# espuno.net
KiCad netlist of a schematic drawn in EAGLE
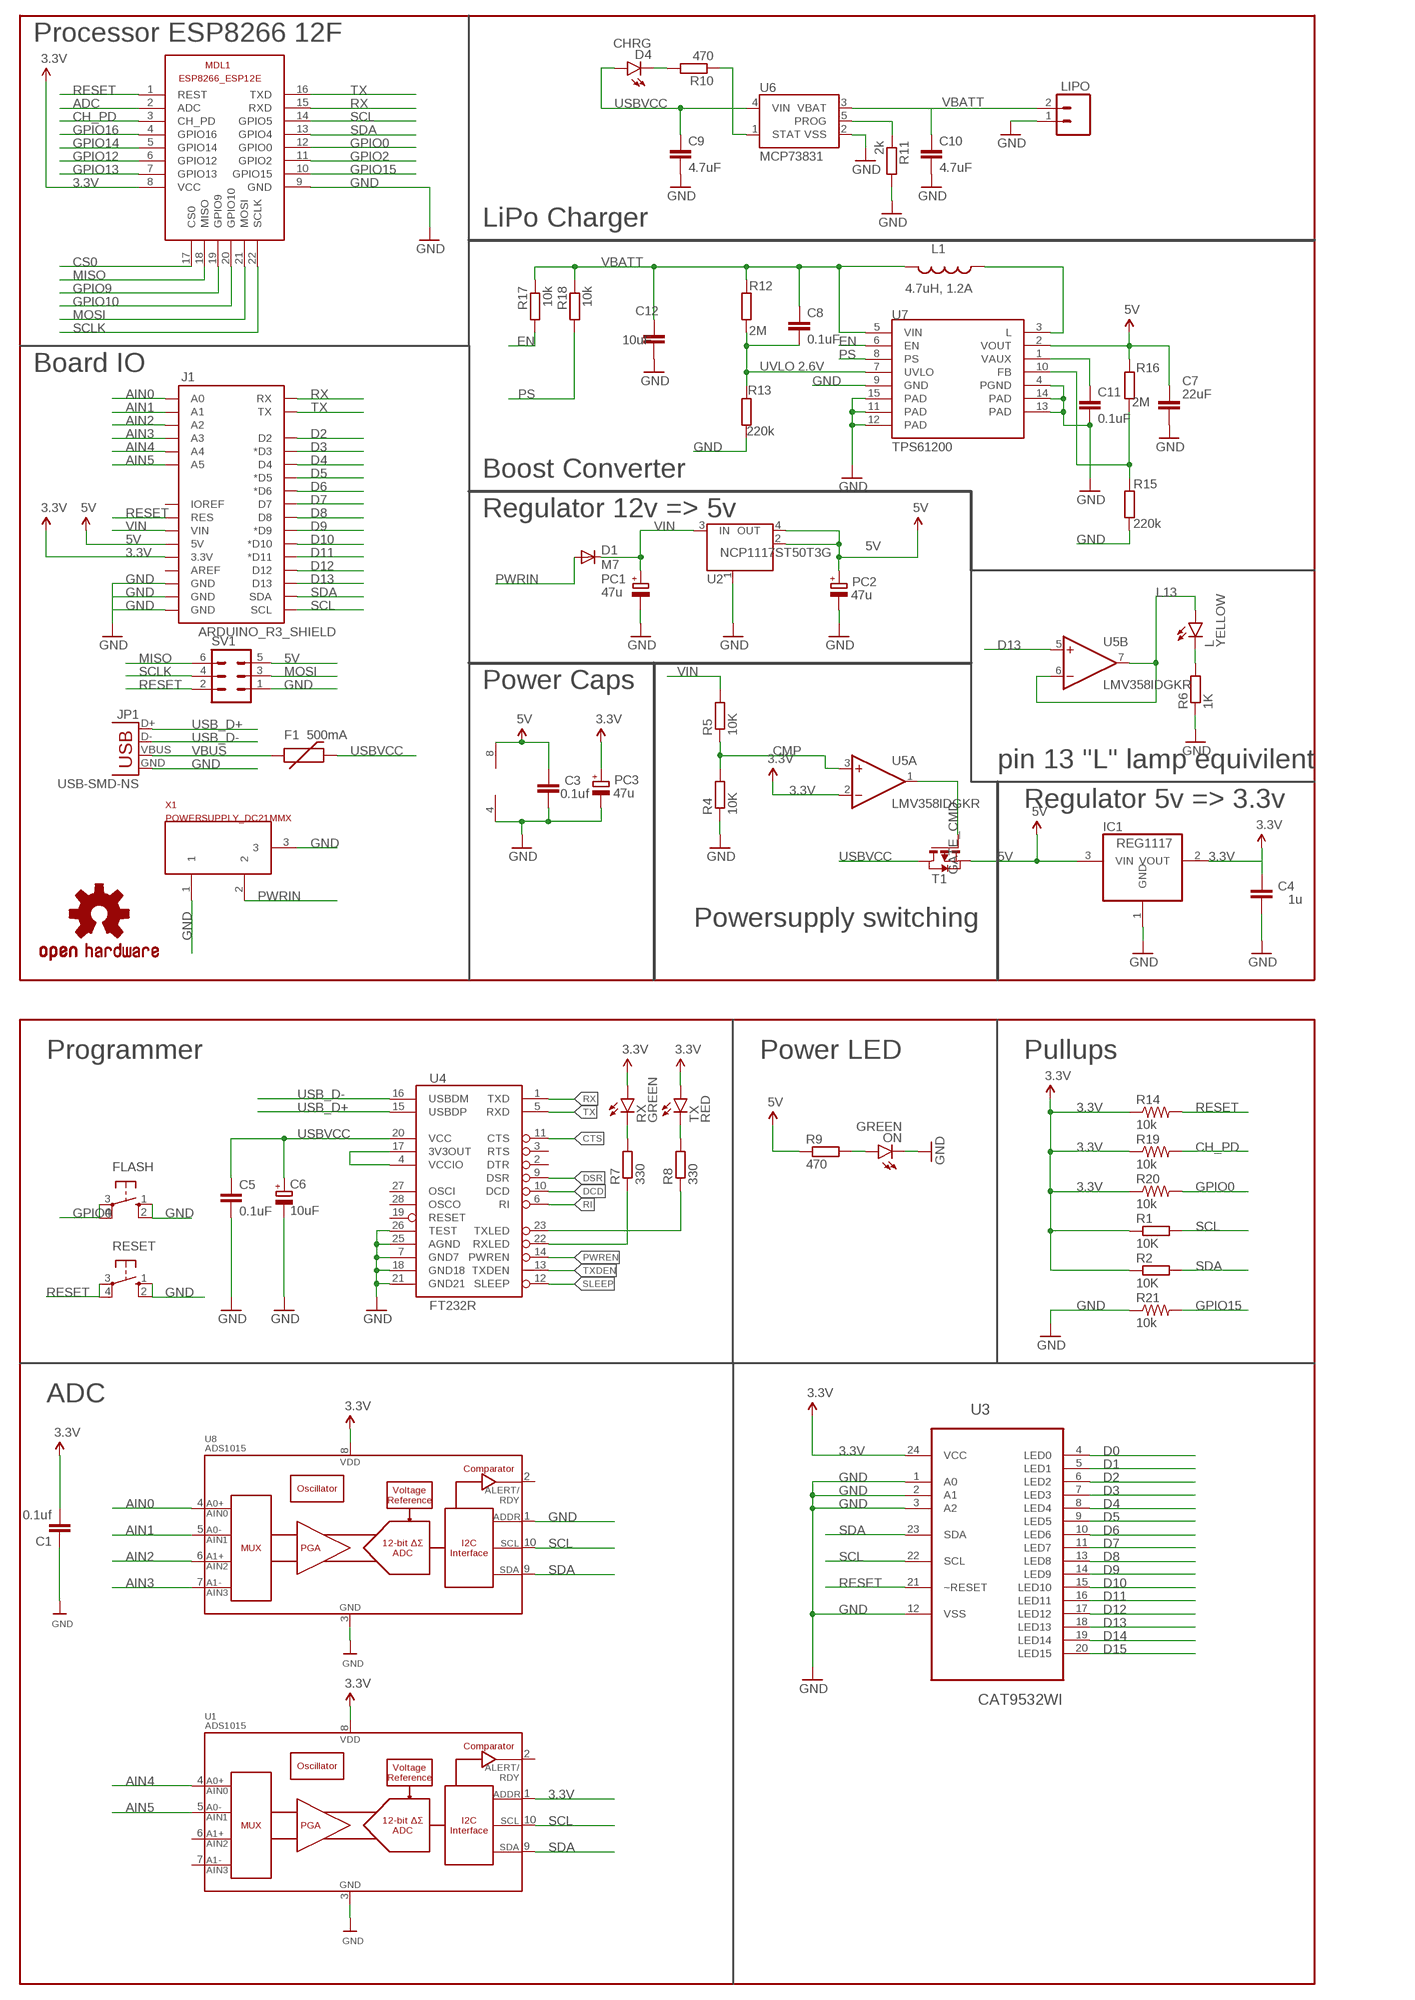
[diagram p0: schematic, sheet 1]

(export (version "E")
  (design (tool "Eeschema 10.0.6"))
  (components
    (comp (ref "C1")
      (value "0.1uf")
      (footprint "eagle-import:1206")
      (libsource (lib "eagle-import") (part "CAP1206"))
    )
    (comp (ref "C3")
      (value "0.1uf")
      (footprint "eagle-import:C1206K")
      (libsource (lib "eagle-import") (part "C-EUC1206K"))
    )
    (comp (ref "C4")
      (value "1u")
      (footprint "eagle-import:C1206K")
      (libsource (lib "eagle-import") (part "C-EUC1206K"))
    )
    (comp (ref "C5")
      (value "0.1uF")
      (footprint "eagle-import:C1206K")
      (libsource (lib "eagle-import") (part "C-EUC1206K"))
    )
    (comp (ref "C6")
      (value "10uF")
      (footprint "eagle-import:SMC_A")
      (libsource (lib "eagle-import") (part "CPOL-EUSMCA"))
    )
    (comp (ref "C7")
      (value "22uF")
      (footprint "eagle-import:C1206K")
      (libsource (lib "eagle-import") (part "C-EUC1206K"))
    )
    (comp (ref "C8")
      (value "0.1uF")
      (footprint "eagle-import:C1206K")
      (libsource (lib "eagle-import") (part "C-EUC1206K"))
    )
    (comp (ref "C9")
      (value "4.7uF")
      (footprint "eagle-import:C1206K")
      (libsource (lib "eagle-import") (part "C-EUC1206K"))
    )
    (comp (ref "C10")
      (value "4.7uF")
      (footprint "eagle-import:C1206K")
      (libsource (lib "eagle-import") (part "C-EUC1206K"))
    )
    (comp (ref "C11")
      (value "0.1uF")
      (footprint "eagle-import:C1206K")
      (libsource (lib "eagle-import") (part "C-EUC1206K"))
    )
    (comp (ref "C12")
      (value "10uF")
      (footprint "eagle-import:C1206K")
      (libsource (lib "eagle-import") (part "C-EUC1206K"))
    )
    (comp (ref "D1")
      (value "M7")
      (footprint "eagle-import:SMB")
      (libsource (lib "eagle-import") (part "DIODE-SMB"))
    )
    (comp (ref "D4")
      (value "CHRG")
      (footprint "eagle-import:LED-1206")
      (libsource (lib "eagle-import") (part "LED1206"))
    )
    (comp (ref "F1")
      (value "500mA")
      (footprint "eagle-import:PTC-1206")
      (libsource (lib "eagle-import") (part "PTCSMD"))
    )
    (comp (ref "FLASH")
      (value "10-XX")
      (footprint "eagle-import:B3F-10XX")
      (fields (field (name "MPN") "B3F-1000"))
      (libsource (lib "eagle-import") (part "10-XX"))
    )
    (comp (ref "FRAME1")
      (value "FRAME-LETTERNO_PACKAGE")
      (footprint "eagle-import:DUMMY")
      (fields (field (name "DESIGNER") "Nobody"))
      (libsource (lib "eagle-import") (part "FRAME-LETTERNO_PACKAGE"))
    )
    (comp (ref "FRAME2")
      (value "FRAME-LETTERNO_PACKAGE")
      (footprint "eagle-import:DUMMY")
      (fields (field (name "DESIGNER") "Nobody"))
      (libsource (lib "eagle-import") (part "FRAME-LETTERNO_PACKAGE"))
    )
    (comp (ref "IC1")
      (value "REG1117")
      (footprint "eagle-import:SOT223")
      (libsource (lib "eagle-import") (part "REG1117"))
    )
    (comp (ref "J1")
      (value "ARDUINO_R3_SHIELD")
      (footprint "eagle-import:UNO_R3_SHIELD")
      (libsource (lib "eagle-import") (part "ARDUINO_R3_SHIELD"))
    )
    (comp (ref "JP1")
      (value "USB-SMD-NS")
      (footprint "eagle-import:USB-MINIB-NOSTOP")
      (libsource (lib "eagle-import") (part "USB-SMD-NS"))
    )
    (comp (ref "L")
      (value "YELLOW")
      (footprint "eagle-import:LED-1206")
      (libsource (lib "eagle-import") (part "LED1206"))
    )
    (comp (ref "L1")
      (value "4.7uH, 1.2A")
      (footprint "eagle-import:CDRH2D09")
      (libsource (lib "eagle-import") (part "INDUCTOR."))
    )
    (comp (ref "LIPO")
      (value "M02JST-PTH-2")
      (footprint "eagle-import:JST-2-PTH")
      (libsource (lib "eagle-import") (part "M02JST-PTH-2"))
    )
    (comp (ref "LOGO1")
      (value "OSHW-LOGOS")
      (footprint "eagle-import:OSHW-LOGO-S")
      (libsource (lib "eagle-import") (part "OSHW-LOGOS"))
    )
    (comp (ref "MDL1")
      (value "ESP8266-12EESP8266-ESP12E")
      (footprint "eagle-import:ESP8266-ESP12E")
      (libsource (lib "eagle-import") (part "ESP8266-12EESP8266-ESP12E"))
    )
    (comp (ref "ON")
      (value "GREEN")
      (footprint "eagle-import:LED-1206")
      (libsource (lib "eagle-import") (part "LED1206"))
    )
    (comp (ref "PC1")
      (value "47u")
      (footprint "eagle-import:PANASONIC_D")
      (libsource (lib "eagle-import") (part "CPOL-EUD"))
    )
    (comp (ref "PC2")
      (value "47u")
      (footprint "eagle-import:PANASONIC_D")
      (libsource (lib "eagle-import") (part "CPOL-EUD"))
    )
    (comp (ref "PC3")
      (value "47u")
      (footprint "eagle-import:PANASONIC_D")
      (libsource (lib "eagle-import") (part "CPOL-EUD"))
    )
    (comp (ref "R1")
      (value "10K")
      (footprint "eagle-import:M1206")
      (libsource (lib "eagle-import") (part "R-EU_M1206"))
    )
    (comp (ref "R2")
      (value "10K")
      (footprint "eagle-import:M1206")
      (libsource (lib "eagle-import") (part "R-EU_M1206"))
    )
    (comp (ref "R4")
      (value "10K")
      (footprint "eagle-import:M1206")
      (libsource (lib "eagle-import") (part "R-EU_M1206"))
    )
    (comp (ref "R5")
      (value "10K")
      (footprint "eagle-import:M1206")
      (libsource (lib "eagle-import") (part "R-EU_M1206"))
    )
    (comp (ref "R6")
      (value "1K")
      (footprint "eagle-import:M1206")
      (libsource (lib "eagle-import") (part "R-EU_M1206"))
    )
    (comp (ref "R7")
      (value "330")
      (footprint "eagle-import:M1206")
      (libsource (lib "eagle-import") (part "R-EU_M1206"))
    )
    (comp (ref "R8")
      (value "330")
      (footprint "eagle-import:M1206")
      (libsource (lib "eagle-import") (part "R-EU_M1206"))
    )
    (comp (ref "R9")
      (value "470")
      (footprint "eagle-import:M1206")
      (libsource (lib "eagle-import") (part "R-EU_M1206"))
    )
    (comp (ref "R10")
      (value "470")
      (footprint "eagle-import:M1206")
      (libsource (lib "eagle-import") (part "R-EU_M1206"))
    )
    (comp (ref "R11")
      (value "2k")
      (footprint "eagle-import:M1206")
      (libsource (lib "eagle-import") (part "R-EU_M1206"))
    )
    (comp (ref "R12")
      (value "2M")
      (footprint "eagle-import:M1206")
      (libsource (lib "eagle-import") (part "R-EU_M1206"))
    )
    (comp (ref "R13")
      (value "220k")
      (footprint "eagle-import:M1206")
      (libsource (lib "eagle-import") (part "R-EU_M1206"))
    )
    (comp (ref "R14")
      (value "10k")
      (footprint "eagle-import:1206")
      (libsource (lib "eagle-import") (part "RESISTOR1206"))
    )
    (comp (ref "R15")
      (value "220k")
      (footprint "eagle-import:M1206")
      (libsource (lib "eagle-import") (part "R-EU_M1206"))
    )
    (comp (ref "R16")
      (value "2M")
      (footprint "eagle-import:M1206")
      (libsource (lib "eagle-import") (part "R-EU_M1206"))
    )
    (comp (ref "R17")
      (value "10k")
      (footprint "eagle-import:M1206")
      (libsource (lib "eagle-import") (part "R-EU_M1206"))
    )
    (comp (ref "R18")
      (value "10k")
      (footprint "eagle-import:M1206")
      (libsource (lib "eagle-import") (part "R-EU_M1206"))
    )
    (comp (ref "R19")
      (value "10k")
      (footprint "eagle-import:1206")
      (libsource (lib "eagle-import") (part "RESISTOR1206"))
    )
    (comp (ref "R20")
      (value "10k")
      (footprint "eagle-import:1206")
      (libsource (lib "eagle-import") (part "RESISTOR1206"))
    )
    (comp (ref "R21")
      (value "10k")
      (footprint "eagle-import:1206")
      (libsource (lib "eagle-import") (part "RESISTOR1206"))
    )
    (comp (ref "RESET")
      (value "10-XX")
      (footprint "eagle-import:B3F-10XX")
      (fields (field (name "MPN") "B3F-1000"))
      (libsource (lib "eagle-import") (part "10-XX"))
    )
    (comp (ref "RX")
      (value "GREEN")
      (footprint "eagle-import:LED-1206")
      (libsource (lib "eagle-import") (part "LED1206"))
    )
    (comp (ref "SV1")
      (value "MA03-2")
      (footprint "eagle-import:MA03-2")
      (libsource (lib "eagle-import") (part "MA03-2"))
    )
    (comp (ref "T1")
      (value "FDN340P")
      (footprint "eagle-import:SOT-23")
      (libsource (lib "eagle-import") (part "PMOSSOT23"))
    )
    (comp (ref "TX")
      (value "RED")
      (footprint "eagle-import:LED-1206")
      (libsource (lib "eagle-import") (part "LED1206"))
    )
    (comp (ref "U1")
      (value "ADS1015")
      (footprint "eagle-import:MSOP10")
      (libsource (lib "eagle-import") (part "ADS1015"))
    )
    (comp (ref "U2")
      (value "NCP1117ST50T3G")
      (footprint "eagle-import:SOT223")
      (libsource (lib "eagle-import") (part "MC33269ST-3.3T3"))
    )
    (comp (ref "U3")
      (value "CAT9532WI")
      (footprint "eagle-import:SOIC127P1031X265-24N")
      (fields (field (name "MPN") "CAT9532WI."))
      (libsource (lib "eagle-import") (part "CAT9532WI"))
    )
    (comp (ref "U4")
      (value "FT232R")
      (footprint "eagle-import:SSOP28DB")
      (libsource (lib "eagle-import") (part "FT232RLSSOP"))
    )
    (comp (ref "U5")
      (value "LMV358IDGKR")
      (footprint "eagle-import:MSOP08")
      (libsource (lib "eagle-import") (part "LMV358?MMX"))
    )
    (comp (ref "U6")
      (value "MCP73831")
      (footprint "eagle-import:SOT23-5")
      (libsource (lib "eagle-import") (part "MCP73831"))
    )
    (comp (ref "U7")
      (value "TPS61200")
      (footprint "eagle-import:QFN-10_PAD")
      (libsource (lib "eagle-import") (part "TPS61200"))
    )
    (comp (ref "U8")
      (value "ADS1015")
      (footprint "eagle-import:MSOP10")
      (libsource (lib "eagle-import") (part "ADS1015"))
    )
    (comp (ref "X1")
      (value "POWERSUPPLY_DC21MMX")
      (footprint "eagle-import:POWERSUPPLY_DC-21MM")
      (libsource (lib "eagle-import") (part "POWERSUPPLY_DC21MMX"))
    )
  )
  (nets
    (net (code "1") (name "/ADC") (class "Default")
      (node (ref "MDL1") (pin "2") (pinfunction "ADC_2") (pintype "bidirectional"))
    )
    (net (code "2") (name "/AIN0") (class "Default")
      (node (ref "J1") (pin "A0") (pinfunction "A0_A0") (pintype "bidirectional"))
      (node (ref "U8") (pin "4") (pinfunction "AIN0_4") (pintype "bidirectional"))
    )
    (net (code "3") (name "/AIN1") (class "Default")
      (node (ref "J1") (pin "A1") (pinfunction "A1_A1") (pintype "bidirectional"))
      (node (ref "U8") (pin "5") (pinfunction "AIN1_5") (pintype "bidirectional"))
    )
    (net (code "4") (name "/AIN2") (class "Default")
      (node (ref "J1") (pin "A2") (pinfunction "A2_A2") (pintype "bidirectional"))
      (node (ref "U8") (pin "6") (pinfunction "AIN2_6") (pintype "bidirectional"))
    )
    (net (code "5") (name "/AIN3") (class "Default")
      (node (ref "J1") (pin "A3") (pinfunction "A3_A3") (pintype "bidirectional"))
      (node (ref "U8") (pin "7") (pinfunction "AIN3_7") (pintype "bidirectional"))
    )
    (net (code "6") (name "/AIN4") (class "Default")
      (node (ref "J1") (pin "A4") (pinfunction "A4_A4") (pintype "bidirectional"))
      (node (ref "U1") (pin "4") (pinfunction "AIN0_4") (pintype "bidirectional"))
    )
    (net (code "7") (name "/AIN5") (class "Default")
      (node (ref "J1") (pin "A5") (pinfunction "A5_A5") (pintype "bidirectional"))
      (node (ref "U1") (pin "5") (pinfunction "AIN1_5") (pintype "bidirectional"))
    )
    (net (code "8") (name "/CH_PD") (class "Default")
      (node (ref "MDL1") (pin "3") (pinfunction "CH_PD_3") (pintype "bidirectional"))
      (node (ref "R19") (pin "2") (pinfunction "2_2") (pintype "passive"))
    )
    (net (code "9") (name "/CMP") (class "Default")
      (node (ref "R4") (pin "2") (pinfunction "2_2") (pintype "passive"))
      (node (ref "R5") (pin "1") (pinfunction "1_1") (pintype "passive"))
      (node (ref "U5") (pin "3") (pinfunction "+IN_3") (pintype "input"))
    )
    (net (code "10") (name "/CS0") (class "Default")
      (node (ref "MDL1") (pin "17") (pinfunction "CS0_17") (pintype "bidirectional"))
    )
    (net (code "11") (name "/D0") (class "Default")
      (node (ref "U3") (pin "4") (pinfunction "LED0_4") (pintype "output"))
    )
    (net (code "12") (name "/D1") (class "Default")
      (node (ref "U3") (pin "5") (pinfunction "LED1_5") (pintype "output"))
    )
    (net (code "13") (name "/D2") (class "Default")
      (node (ref "J1") (pin "D2") (pinfunction "D2_D2") (pintype "bidirectional"))
      (node (ref "U3") (pin "6") (pinfunction "LED2_6") (pintype "output"))
    )
    (net (code "14") (name "/D3") (class "Default")
      (node (ref "J1") (pin "D3") (pinfunction "*D3_D3") (pintype "bidirectional"))
      (node (ref "U3") (pin "7") (pinfunction "LED3_7") (pintype "output"))
    )
    (net (code "15") (name "/D4") (class "Default")
      (node (ref "J1") (pin "D4") (pinfunction "D4_D4") (pintype "bidirectional"))
      (node (ref "U3") (pin "8") (pinfunction "LED4_8") (pintype "output"))
    )
    (net (code "16") (name "/D5") (class "Default")
      (node (ref "J1") (pin "D5") (pinfunction "*D5_D5") (pintype "bidirectional"))
      (node (ref "U3") (pin "9") (pinfunction "LED5_9") (pintype "output"))
    )
    (net (code "17") (name "/D6") (class "Default")
      (node (ref "J1") (pin "D6") (pinfunction "*D6_D6") (pintype "bidirectional"))
      (node (ref "U3") (pin "10") (pinfunction "LED6_10") (pintype "output"))
    )
    (net (code "18") (name "/D7") (class "Default")
      (node (ref "J1") (pin "D7") (pinfunction "D7_D7") (pintype "bidirectional"))
      (node (ref "U3") (pin "11") (pinfunction "LED7_11") (pintype "output"))
    )
    (net (code "19") (name "/D8") (class "Default")
      (node (ref "J1") (pin "D8") (pinfunction "D8_D8") (pintype "bidirectional"))
      (node (ref "U3") (pin "13") (pinfunction "LED8_13") (pintype "output"))
    )
    (net (code "20") (name "/D9") (class "Default")
      (node (ref "J1") (pin "D9") (pinfunction "*D9_D9") (pintype "bidirectional"))
      (node (ref "U3") (pin "14") (pinfunction "LED9_14") (pintype "output"))
    )
    (net (code "21") (name "/D10") (class "Default")
      (node (ref "J1") (pin "D10") (pinfunction "*D10_D10") (pintype "bidirectional"))
      (node (ref "U3") (pin "15") (pinfunction "LED10_15") (pintype "output"))
    )
    (net (code "22") (name "/D11") (class "Default")
      (node (ref "J1") (pin "D11") (pinfunction "*D11_D11") (pintype "bidirectional"))
      (node (ref "U3") (pin "16") (pinfunction "LED11_16") (pintype "output"))
    )
    (net (code "23") (name "/D12") (class "Default")
      (node (ref "J1") (pin "D12") (pinfunction "D12_D12") (pintype "bidirectional"))
      (node (ref "U3") (pin "17") (pinfunction "LED12_17") (pintype "output"))
    )
    (net (code "24") (name "/D13") (class "Default")
      (node (ref "J1") (pin "D13") (pinfunction "D13_D13") (pintype "bidirectional"))
      (node (ref "U3") (pin "18") (pinfunction "LED13_18") (pintype "output"))
      (node (ref "U5") (pin "5") (pinfunction "+IN_5") (pintype "input"))
    )
    (net (code "25") (name "/D14") (class "Default")
      (node (ref "U3") (pin "19") (pinfunction "LED14_19") (pintype "output"))
    )
    (net (code "26") (name "/D15") (class "Default")
      (node (ref "U3") (pin "20") (pinfunction "LED15_20") (pintype "output"))
    )
    (net (code "27") (name "/EN") (class "Default")
      (node (ref "R17") (pin "2") (pinfunction "2_2") (pintype "passive"))
      (node (ref "U7") (pin "6") (pinfunction "EN_6") (pintype "input"))
    )
    (net (code "28") (name "/GATE_CMD") (class "Default")
      (node (ref "T1") (pin "3") (pinfunction "G_3") (pintype "passive"))
      (node (ref "U5") (pin "1") (pinfunction "OUT_1") (pintype "output"))
    )
    (net (code "29") (name "/GPIO0") (class "Default")
      (node (ref "FLASH") (pin "3") (pinfunction "P_3") (pintype "passive"))
      (node (ref "FLASH") (pin "4") (pinfunction "P1_4") (pintype "passive"))
      (node (ref "MDL1") (pin "12") (pinfunction "GPIO0_12") (pintype "bidirectional"))
      (node (ref "R20") (pin "2") (pinfunction "2_2") (pintype "passive"))
    )
    (net (code "30") (name "/GPIO2") (class "Default")
      (node (ref "MDL1") (pin "11") (pinfunction "GPIO2_11") (pintype "bidirectional"))
    )
    (net (code "31") (name "/GPIO9") (class "Default")
      (node (ref "MDL1") (pin "19") (pinfunction "GPIO9_19") (pintype "bidirectional"))
    )
    (net (code "32") (name "/GPIO10") (class "Default")
      (node (ref "MDL1") (pin "20") (pinfunction "GPIO10_20") (pintype "bidirectional"))
    )
    (net (code "33") (name "/GPIO12") (class "Default")
      (node (ref "MDL1") (pin "6") (pinfunction "GPIO12_6") (pintype "bidirectional"))
    )
    (net (code "34") (name "/GPIO13") (class "Default")
      (node (ref "MDL1") (pin "7") (pinfunction "GPIO13_7") (pintype "bidirectional"))
    )
    (net (code "35") (name "/GPIO14") (class "Default")
      (node (ref "MDL1") (pin "5") (pinfunction "GPIO14_5") (pintype "bidirectional"))
    )
    (net (code "36") (name "/GPIO15") (class "Default")
      (node (ref "MDL1") (pin "10") (pinfunction "GPIO15_10") (pintype "bidirectional"))
      (node (ref "R21") (pin "2") (pinfunction "2_2") (pintype "passive"))
    )
    (net (code "37") (name "/GPIO16") (class "Default")
      (node (ref "MDL1") (pin "4") (pinfunction "GPIO16_4") (pintype "bidirectional"))
    )
    (net (code "38") (name "/L13") (class "Default")
      (node (ref "L") (pin "A") (pinfunction "A_A") (pintype "passive"))
      (node (ref "U5") (pin "6") (pinfunction "-IN_6") (pintype "input"))
      (node (ref "U5") (pin "7") (pinfunction "OUT_7") (pintype "output"))
    )
    (net (code "39") (name "/MISO") (class "Default")
      (node (ref "MDL1") (pin "18") (pinfunction "MISO_18") (pintype "bidirectional"))
      (node (ref "SV1") (pin "6") (pinfunction "6_6") (pintype "passive"))
    )
    (net (code "40") (name "/MOSI") (class "Default")
      (node (ref "MDL1") (pin "21") (pinfunction "MOSI_21") (pintype "bidirectional"))
      (node (ref "SV1") (pin "3") (pinfunction "3_3") (pintype "passive"))
    )
    (net (code "41") (name "/PS") (class "Default")
      (node (ref "R18") (pin "2") (pinfunction "2_2") (pintype "passive"))
      (node (ref "U7") (pin "8") (pinfunction "PS_8") (pintype "input"))
    )
    (net (code "42") (name "/PWRIN") (class "Default")
      (node (ref "D1") (pin "A") (pinfunction "A_A") (pintype "passive"))
      (node (ref "X1") (pin "2") (pinfunction "2_2") (pintype "power_in"))
    )
    (net (code "43") (name "/RESET") (class "Default")
      (node (ref "J1") (pin "RES") (pinfunction "RES_RES") (pintype "bidirectional"))
      (node (ref "MDL1") (pin "1") (pinfunction "REST_1") (pintype "bidirectional"))
      (node (ref "R14") (pin "2") (pinfunction "2_2") (pintype "passive"))
      (node (ref "RESET") (pin "3") (pinfunction "P_3") (pintype "passive"))
      (node (ref "RESET") (pin "4") (pinfunction "P1_4") (pintype "passive"))
      (node (ref "SV1") (pin "2") (pinfunction "2_2") (pintype "passive"))
      (node (ref "U3") (pin "21") (pinfunction "~{RESET}_21") (pintype "input"))
    )
    (net (code "44") (name "/SCL") (class "Default")
      (node (ref "J1") (pin "SCL") (pinfunction "SCL_SCL") (pintype "bidirectional"))
      (node (ref "MDL1") (pin "14") (pinfunction "GPIO5_14") (pintype "bidirectional"))
      (node (ref "R1") (pin "2") (pinfunction "2_2") (pintype "passive"))
      (node (ref "U1") (pin "10") (pinfunction "SCL_10") (pintype "bidirectional"))
      (node (ref "U3") (pin "22") (pinfunction "SCL_22") (pintype "input"))
      (node (ref "U8") (pin "10") (pinfunction "SCL_10") (pintype "bidirectional"))
    )
    (net (code "45") (name "/SCLK") (class "Default")
      (node (ref "MDL1") (pin "22") (pinfunction "SCLK_22") (pintype "bidirectional"))
      (node (ref "SV1") (pin "4") (pinfunction "4_4") (pintype "passive"))
    )
    (net (code "46") (name "/SDA") (class "Default")
      (node (ref "J1") (pin "SDA") (pinfunction "SDA_SDA") (pintype "bidirectional"))
      (node (ref "MDL1") (pin "13") (pinfunction "GPIO4_13") (pintype "bidirectional"))
      (node (ref "R2") (pin "2") (pinfunction "2_2") (pintype "passive"))
      (node (ref "U1") (pin "9") (pinfunction "SDA_9") (pintype "bidirectional"))
      (node (ref "U3") (pin "23") (pinfunction "SDA_23") (pintype "input"))
      (node (ref "U8") (pin "9") (pinfunction "SDA_9") (pintype "bidirectional"))
    )
    (net (code "47") (name "/USBVCC") (class "Default")
      (node (ref "C5") (pin "1") (pinfunction "1_1") (pintype "passive"))
      (node (ref "C6") (pin "+") (pinfunction "+_+") (pintype "passive"))
      (node (ref "C9") (pin "1") (pinfunction "1_1") (pintype "passive"))
      (node (ref "D4") (pin "A") (pinfunction "A_A") (pintype "passive"))
      (node (ref "F1") (pin "2") (pinfunction "2_2") (pintype "bidirectional"))
      (node (ref "T1") (pin "1") (pinfunction "D_1") (pintype "passive"))
      (node (ref "U4") (pin "20") (pinfunction "VCC_20") (pintype "power_in"))
      (node (ref "U6") (pin "4") (pinfunction "VIN_4") (pintype "power_in"))
    )
    (net (code "48") (name "/USB_D+") (class "Default")
      (node (ref "JP1") (pin "D+") (pinfunction "D+_D+") (pintype "bidirectional"))
      (node (ref "U4") (pin "15") (pinfunction "USBDP_15") (pintype "bidirectional"))
    )
    (net (code "49") (name "/USB_D-") (class "Default")
      (node (ref "JP1") (pin "D-") (pinfunction "D-_D-") (pintype "bidirectional"))
      (node (ref "U4") (pin "16") (pinfunction "USBDM_16") (pintype "bidirectional"))
    )
    (net (code "50") (name "/VBATT") (class "Default")
      (node (ref "C10") (pin "1") (pinfunction "1_1") (pintype "passive"))
      (node (ref "C12") (pin "1") (pinfunction "1_1") (pintype "passive"))
      (node (ref "C8") (pin "1") (pinfunction "1_1") (pintype "passive"))
      (node (ref "L1") (pin "P$2") (pinfunction "2_P$2") (pintype "passive"))
      (node (ref "LIPO") (pin "2") (pinfunction "2_2") (pintype "passive"))
      (node (ref "R12") (pin "2") (pinfunction "2_2") (pintype "passive"))
      (node (ref "R17") (pin "1") (pinfunction "1_1") (pintype "passive"))
      (node (ref "R18") (pin "1") (pinfunction "1_1") (pintype "passive"))
      (node (ref "U6") (pin "3") (pinfunction "VBAT_3") (pintype "power_in"))
      (node (ref "U7") (pin "5") (pinfunction "VIN_5") (pintype "power_in"))
    )
    (net (code "51") (name "/VBUS") (class "Default")
      (node (ref "F1") (pin "1") (pinfunction "1_1") (pintype "bidirectional"))
      (node (ref "JP1") (pin "VBUS") (pinfunction "VBUS_VBUS") (pintype "bidirectional"))
    )
    (net (code "52") (name "/VIN") (class "Default")
      (node (ref "D1") (pin "C") (pinfunction "C_C") (pintype "passive"))
      (node (ref "J1") (pin "VIN") (pinfunction "VIN_VIN") (pintype "bidirectional"))
      (node (ref "PC1") (pin "+") (pinfunction "+_+") (pintype "passive"))
      (node (ref "R5") (pin "2") (pinfunction "2_2") (pintype "passive"))
      (node (ref "U2") (pin "3") (pinfunction "IN_3") (pintype "input"))
    )
    (net (code "53") (name "3.3V") (class "Default")
      (node (ref "C1") (pin "2") (pinfunction "2_2") (pintype "passive"))
      (node (ref "C4") (pin "2") (pinfunction "2_2") (pintype "passive"))
      (node (ref "IC1") (pin "2") (pinfunction "VOUT_2") (pintype "output"))
      (node (ref "J1") (pin "3.3V") (pinfunction "3.3V_3.3V") (pintype "bidirectional"))
      (node (ref "MDL1") (pin "8") (pinfunction "VCC_8") (pintype "bidirectional"))
      (node (ref "PC3") (pin "+") (pinfunction "+_+") (pintype "passive"))
      (node (ref "R1") (pin "1") (pinfunction "1_1") (pintype "passive"))
      (node (ref "R14") (pin "1") (pinfunction "1_1") (pintype "passive"))
      (node (ref "R19") (pin "1") (pinfunction "1_1") (pintype "passive"))
      (node (ref "R2") (pin "1") (pinfunction "1_1") (pintype "passive"))
      (node (ref "R20") (pin "1") (pinfunction "1_1") (pintype "passive"))
      (node (ref "RX") (pin "A") (pinfunction "A_A") (pintype "passive"))
      (node (ref "TX") (pin "A") (pinfunction "A_A") (pintype "passive"))
      (node (ref "U1") (pin "1") (pinfunction "ADDR_1") (pintype "bidirectional"))
      (node (ref "U1") (pin "8") (pinfunction "VDD_8") (pintype "bidirectional"))
      (node (ref "U3") (pin "24") (pinfunction "VCC_24") (pintype "power_in"))
      (node (ref "U5") (pin "2") (pinfunction "-IN_2") (pintype "input"))
      (node (ref "U8") (pin "8") (pinfunction "VDD_8") (pintype "bidirectional"))
    )
    (net (code "54") (name "5V") (class "Default")
      (node (ref "C3") (pin "2") (pinfunction "2_2") (pintype "passive"))
      (node (ref "C7") (pin "1") (pinfunction "1_1") (pintype "passive"))
      (node (ref "IC1") (pin "3") (pinfunction "VIN_3") (pintype "input"))
      (node (ref "J1") (pin "5V") (pinfunction "5V_5V") (pintype "bidirectional"))
      (node (ref "PC2") (pin "+") (pinfunction "+_+") (pintype "passive"))
      (node (ref "R16") (pin "2") (pinfunction "2_2") (pintype "passive"))
      (node (ref "R9") (pin "1") (pinfunction "1_1") (pintype "passive"))
      (node (ref "SV1") (pin "5") (pinfunction "5_5") (pintype "passive"))
      (node (ref "T1") (pin "2") (pinfunction "S_2") (pintype "passive"))
      (node (ref "U2") (pin "2") (pinfunction "OUT_2") (pintype "passive"))
      (node (ref "U2") (pin "4") (pinfunction "OUT_4") (pintype "passive"))
      (node (ref "U5") (pin "8") (pinfunction "V+_8") (pintype "power_in"))
      (node (ref "U7") (pin "2") (pinfunction "VOUT_2") (pintype "passive"))
    )
    (net (code "55") (name "CTS") (class "Default")
      (node (ref "U4") (pin "11") (pinfunction "CTS_11") (pintype "input"))
    )
    (net (code "56") (name "DCD") (class "Default")
      (node (ref "U4") (pin "10") (pinfunction "DCD_10") (pintype "input"))
    )
    (net (code "57") (name "DSR") (class "Default")
      (node (ref "U4") (pin "9") (pinfunction "DSR_9") (pintype "input"))
    )
    (net (code "58") (name "GND") (class "Default")
      (node (ref "C1") (pin "1") (pinfunction "1_1") (pintype "passive"))
      (node (ref "C10") (pin "2") (pinfunction "2_2") (pintype "passive"))
      (node (ref "C11") (pin "2") (pinfunction "2_2") (pintype "passive"))
      (node (ref "C12") (pin "2") (pinfunction "2_2") (pintype "passive"))
      (node (ref "C3") (pin "1") (pinfunction "1_1") (pintype "passive"))
      (node (ref "C4") (pin "1") (pinfunction "1_1") (pintype "passive"))
      (node (ref "C5") (pin "2") (pinfunction "2_2") (pintype "passive"))
      (node (ref "C6") (pin "-") (pinfunction "-_-") (pintype "passive"))
      (node (ref "C7") (pin "2") (pinfunction "2_2") (pintype "passive"))
      (node (ref "C9") (pin "2") (pinfunction "2_2") (pintype "passive"))
      (node (ref "FLASH") (pin "1") (pinfunction "S_1") (pintype "passive"))
      (node (ref "FLASH") (pin "2") (pinfunction "S1_2") (pintype "passive"))
      (node (ref "IC1") (pin "1") (pinfunction "GND_1") (pintype "power_in"))
      (node (ref "J1") (pin "GND@0") (pinfunction "GND_GND@0") (pintype "bidirectional"))
      (node (ref "J1") (pin "GND@1") (pinfunction "GND_GND@1") (pintype "bidirectional"))
      (node (ref "J1") (pin "GND@2") (pinfunction "GND_GND@2") (pintype "bidirectional"))
      (node (ref "JP1") (pin "GND") (pinfunction "GND_GND") (pintype "bidirectional"))
      (node (ref "LIPO") (pin "1") (pinfunction "1_1") (pintype "passive"))
      (node (ref "MDL1") (pin "9") (pinfunction "GND_9") (pintype "bidirectional"))
      (node (ref "ON") (pin "C") (pinfunction "C_C") (pintype "passive"))
      (node (ref "PC1") (pin "-") (pinfunction "-_-") (pintype "passive"))
      (node (ref "PC2") (pin "-") (pinfunction "-_-") (pintype "passive"))
      (node (ref "PC3") (pin "-") (pinfunction "-_-") (pintype "passive"))
      (node (ref "R11") (pin "2") (pinfunction "2_2") (pintype "passive"))
      (node (ref "R13") (pin "1") (pinfunction "1_1") (pintype "passive"))
      (node (ref "R15") (pin "1") (pinfunction "1_1") (pintype "passive"))
      (node (ref "R21") (pin "1") (pinfunction "1_1") (pintype "passive"))
      (node (ref "R4") (pin "1") (pinfunction "1_1") (pintype "passive"))
      (node (ref "R6") (pin "1") (pinfunction "1_1") (pintype "passive"))
      (node (ref "RESET") (pin "1") (pinfunction "S_1") (pintype "passive"))
      (node (ref "RESET") (pin "2") (pinfunction "S1_2") (pintype "passive"))
      (node (ref "SV1") (pin "1") (pinfunction "1_1") (pintype "passive"))
      (node (ref "U1") (pin "3") (pinfunction "VSS_3") (pintype "bidirectional"))
      (node (ref "U2") (pin "1") (pinfunction "GND/ADJ_1") (pintype "input"))
      (node (ref "U3") (pin "1") (pinfunction "A0_1") (pintype "input"))
      (node (ref "U3") (pin "12") (pinfunction "VSS_12") (pintype "input"))
      (node (ref "U3") (pin "2") (pinfunction "A1_2") (pintype "input"))
      (node (ref "U3") (pin "3") (pinfunction "A2_3") (pintype "input"))
      (node (ref "U4") (pin "18") (pinfunction "GND18_18") (pintype "power_in"))
      (node (ref "U4") (pin "21") (pinfunction "GND21_21") (pintype "power_in"))
      (node (ref "U4") (pin "25") (pinfunction "AGND_25") (pintype "power_in"))
      (node (ref "U4") (pin "26") (pinfunction "TEST_26") (pintype "input"))
      (node (ref "U4") (pin "7") (pinfunction "GND7_7") (pintype "power_in"))
      (node (ref "U5") (pin "4") (pinfunction "V-_4") (pintype "power_in"))
      (node (ref "U6") (pin "2") (pinfunction "VSS_2") (pintype "power_in"))
      (node (ref "U7") (pin "11") (pinfunction "PAD_11") (pintype "power_in"))
      (node (ref "U7") (pin "12") (pinfunction "PAD_12") (pintype "power_in"))
      (node (ref "U7") (pin "13") (pinfunction "PAD_13") (pintype "power_in"))
      (node (ref "U7") (pin "14") (pinfunction "PAD_14") (pintype "power_in"))
      (node (ref "U7") (pin "15") (pinfunction "PAD_15") (pintype "power_in"))
      (node (ref "U7") (pin "4") (pinfunction "PGND_4") (pintype "power_in"))
      (node (ref "U7") (pin "9") (pinfunction "GND_9") (pintype "power_in"))
      (node (ref "U8") (pin "1") (pinfunction "ADDR_1") (pintype "bidirectional"))
      (node (ref "U8") (pin "3") (pinfunction "VSS_3") (pintype "bidirectional"))
      (node (ref "X1") (pin "1") (pinfunction "1_1") (pintype "power_in"))
      (node (ref "X1") (pin "3") (pinfunction "3_3") (pintype "power_in"))
    )
    (net (code "59") (name "Net-(D4-PadC)") (class "Default")
      (node (ref "D4") (pin "C") (pinfunction "C_C") (pintype "passive"))
      (node (ref "R10") (pin "2") (pinfunction "2_2") (pintype "passive"))
    )
    (net (code "60") (name "Net-(L-PadC)") (class "Default")
      (node (ref "L") (pin "C") (pinfunction "C_C") (pintype "passive"))
      (node (ref "R6") (pin "2") (pinfunction "2_2") (pintype "passive"))
    )
    (net (code "61") (name "Net-(L1-1)") (class "Default")
      (node (ref "L1") (pin "P$1") (pinfunction "1_P$1") (pintype "passive"))
      (node (ref "U7") (pin "3") (pinfunction "L_3") (pintype "passive"))
    )
    (net (code "62") (name "Net-(ON-PadA)") (class "Default")
      (node (ref "ON") (pin "A") (pinfunction "A_A") (pintype "passive"))
      (node (ref "R9") (pin "2") (pinfunction "2_2") (pintype "passive"))
    )
    (net (code "63") (name "Net-(R7-Pad2)") (class "Default")
      (node (ref "R7") (pin "2") (pinfunction "2_2") (pintype "passive"))
      (node (ref "RX") (pin "C") (pinfunction "C_C") (pintype "passive"))
    )
    (net (code "64") (name "Net-(R8-Pad2)") (class "Default")
      (node (ref "R8") (pin "2") (pinfunction "2_2") (pintype "passive"))
      (node (ref "TX") (pin "C") (pinfunction "C_C") (pintype "passive"))
    )
    (net (code "65") (name "Net-(U4-3V3OUT)") (class "Default")
      (node (ref "U4") (pin "17") (pinfunction "3V3OUT_17") (pintype "output"))
      (node (ref "U4") (pin "4") (pinfunction "VCCIO_4") (pintype "power_in"))
    )
    (net (code "66") (name "Net-(U4-RXLED)") (class "Default")
      (node (ref "R7") (pin "1") (pinfunction "1_1") (pintype "passive"))
      (node (ref "U4") (pin "22") (pinfunction "RXLED_22") (pintype "input"))
    )
    (net (code "67") (name "Net-(U4-TXLED)") (class "Default")
      (node (ref "R8") (pin "1") (pinfunction "1_1") (pintype "passive"))
      (node (ref "U4") (pin "23") (pinfunction "TXLED_23") (pintype "input"))
    )
    (net (code "68") (name "Net-(U6-PROG)") (class "Default")
      (node (ref "R11") (pin "1") (pinfunction "1_1") (pintype "passive"))
      (node (ref "U6") (pin "5") (pinfunction "PROG_5") (pintype "input"))
    )
    (net (code "69") (name "Net-(U6-STAT)") (class "Default")
      (node (ref "R10") (pin "1") (pinfunction "1_1") (pintype "passive"))
      (node (ref "U6") (pin "1") (pinfunction "STAT_1") (pintype "output"))
    )
    (net (code "70") (name "Net-(U7-FB)") (class "Default")
      (node (ref "R15") (pin "2") (pinfunction "2_2") (pintype "passive"))
      (node (ref "R16") (pin "1") (pinfunction "1_1") (pintype "passive"))
      (node (ref "U7") (pin "10") (pinfunction "FB_10") (pintype "passive"))
    )
    (net (code "71") (name "Net-(U7-UVLO)") (class "Default")
      (node (ref "C8") (pin "2") (pinfunction "2_2") (pintype "passive"))
      (node (ref "R12") (pin "1") (pinfunction "1_1") (pintype "passive"))
      (node (ref "R13") (pin "2") (pinfunction "2_2") (pintype "passive"))
      (node (ref "U7") (pin "7") (pinfunction "UVLO_7") (pintype "passive"))
    )
    (net (code "72") (name "Net-(U7-VAUX)") (class "Default")
      (node (ref "C11") (pin "1") (pinfunction "1_1") (pintype "passive"))
      (node (ref "U7") (pin "1") (pinfunction "VAUX_1") (pintype "passive"))
    )
    (net (code "73") (name "PWREN") (class "Default")
      (node (ref "U4") (pin "14") (pinfunction "PWREN_14") (pintype "input"))
    )
    (net (code "74") (name "RI") (class "Default")
      (node (ref "U4") (pin "6") (pinfunction "RI_6") (pintype "input"))
    )
    (net (code "75") (name "RX") (class "Default")
      (node (ref "J1") (pin "RX") (pinfunction "RX_RX") (pintype "bidirectional"))
      (node (ref "MDL1") (pin "15") (pinfunction "RXD_15") (pintype "bidirectional"))
      (node (ref "U4") (pin "1") (pinfunction "TXD_1") (pintype "output"))
    )
    (net (code "76") (name "SLEEP") (class "Default")
      (node (ref "U4") (pin "12") (pinfunction "SLEEP_12") (pintype "input"))
    )
    (net (code "77") (name "TX") (class "Default")
      (node (ref "J1") (pin "TX") (pinfunction "TX_TX") (pintype "bidirectional"))
      (node (ref "MDL1") (pin "16") (pinfunction "TXD_16") (pintype "bidirectional"))
      (node (ref "U4") (pin "5") (pinfunction "RXD_5") (pintype "input"))
    )
    (net (code "78") (name "TXDEN") (class "Default")
      (node (ref "U4") (pin "13") (pinfunction "TXDEN_13") (pintype "input"))
    )
    (net (code "79") (name "unconnected-(J1-PadAREF)") (class "Default")
      (node (ref "J1") (pin "AREF") (pinfunction "AREF_AREF") (pintype "bidirectional"))
    )
    (net (code "80") (name "unconnected-(J1-PadIOREF)") (class "Default")
      (node (ref "J1") (pin "IOREF") (pinfunction "IOREF_IOREF") (pintype "bidirectional"))
    )
    (net (code "81") (name "unconnected-(U1-AIN2-Pad6)") (class "Default")
      (node (ref "U1") (pin "6") (pinfunction "AIN2_6") (pintype "bidirectional"))
    )
    (net (code "82") (name "unconnected-(U1-AIN3-Pad7)") (class "Default")
      (node (ref "U1") (pin "7") (pinfunction "AIN3_7") (pintype "bidirectional"))
    )
    (net (code "83") (name "unconnected-(U1-ALERT{slash}RDY-Pad2)") (class "Default")
      (node (ref "U1") (pin "2") (pinfunction "ALERT/RDY_2") (pintype "bidirectional"))
    )
    (net (code "84") (name "unconnected-(U4-DTR-Pad2)") (class "Default")
      (node (ref "U4") (pin "2") (pinfunction "DTR_2") (pintype "output"))
    )
    (net (code "85") (name "unconnected-(U4-OSCI-Pad27)") (class "Default")
      (node (ref "U4") (pin "27") (pinfunction "OSCI_27") (pintype "input"))
    )
    (net (code "86") (name "unconnected-(U4-OSCO-Pad28)") (class "Default")
      (node (ref "U4") (pin "28") (pinfunction "OSCO_28") (pintype "output"))
    )
    (net (code "87") (name "unconnected-(U4-RESET-Pad19)") (class "Default")
      (node (ref "U4") (pin "19") (pinfunction "RESET_19") (pintype "input"))
    )
    (net (code "88") (name "unconnected-(U4-RTS-Pad3)") (class "Default")
      (node (ref "U4") (pin "3") (pinfunction "RTS_3") (pintype "output"))
    )
    (net (code "89") (name "unconnected-(U8-ALERT{slash}RDY-Pad2)") (class "Default")
      (node (ref "U8") (pin "2") (pinfunction "ALERT/RDY_2") (pintype "bidirectional"))
    )
  )
)
